# TUR8535.net
KiCad netlist of a schematic drawn in EAGLE
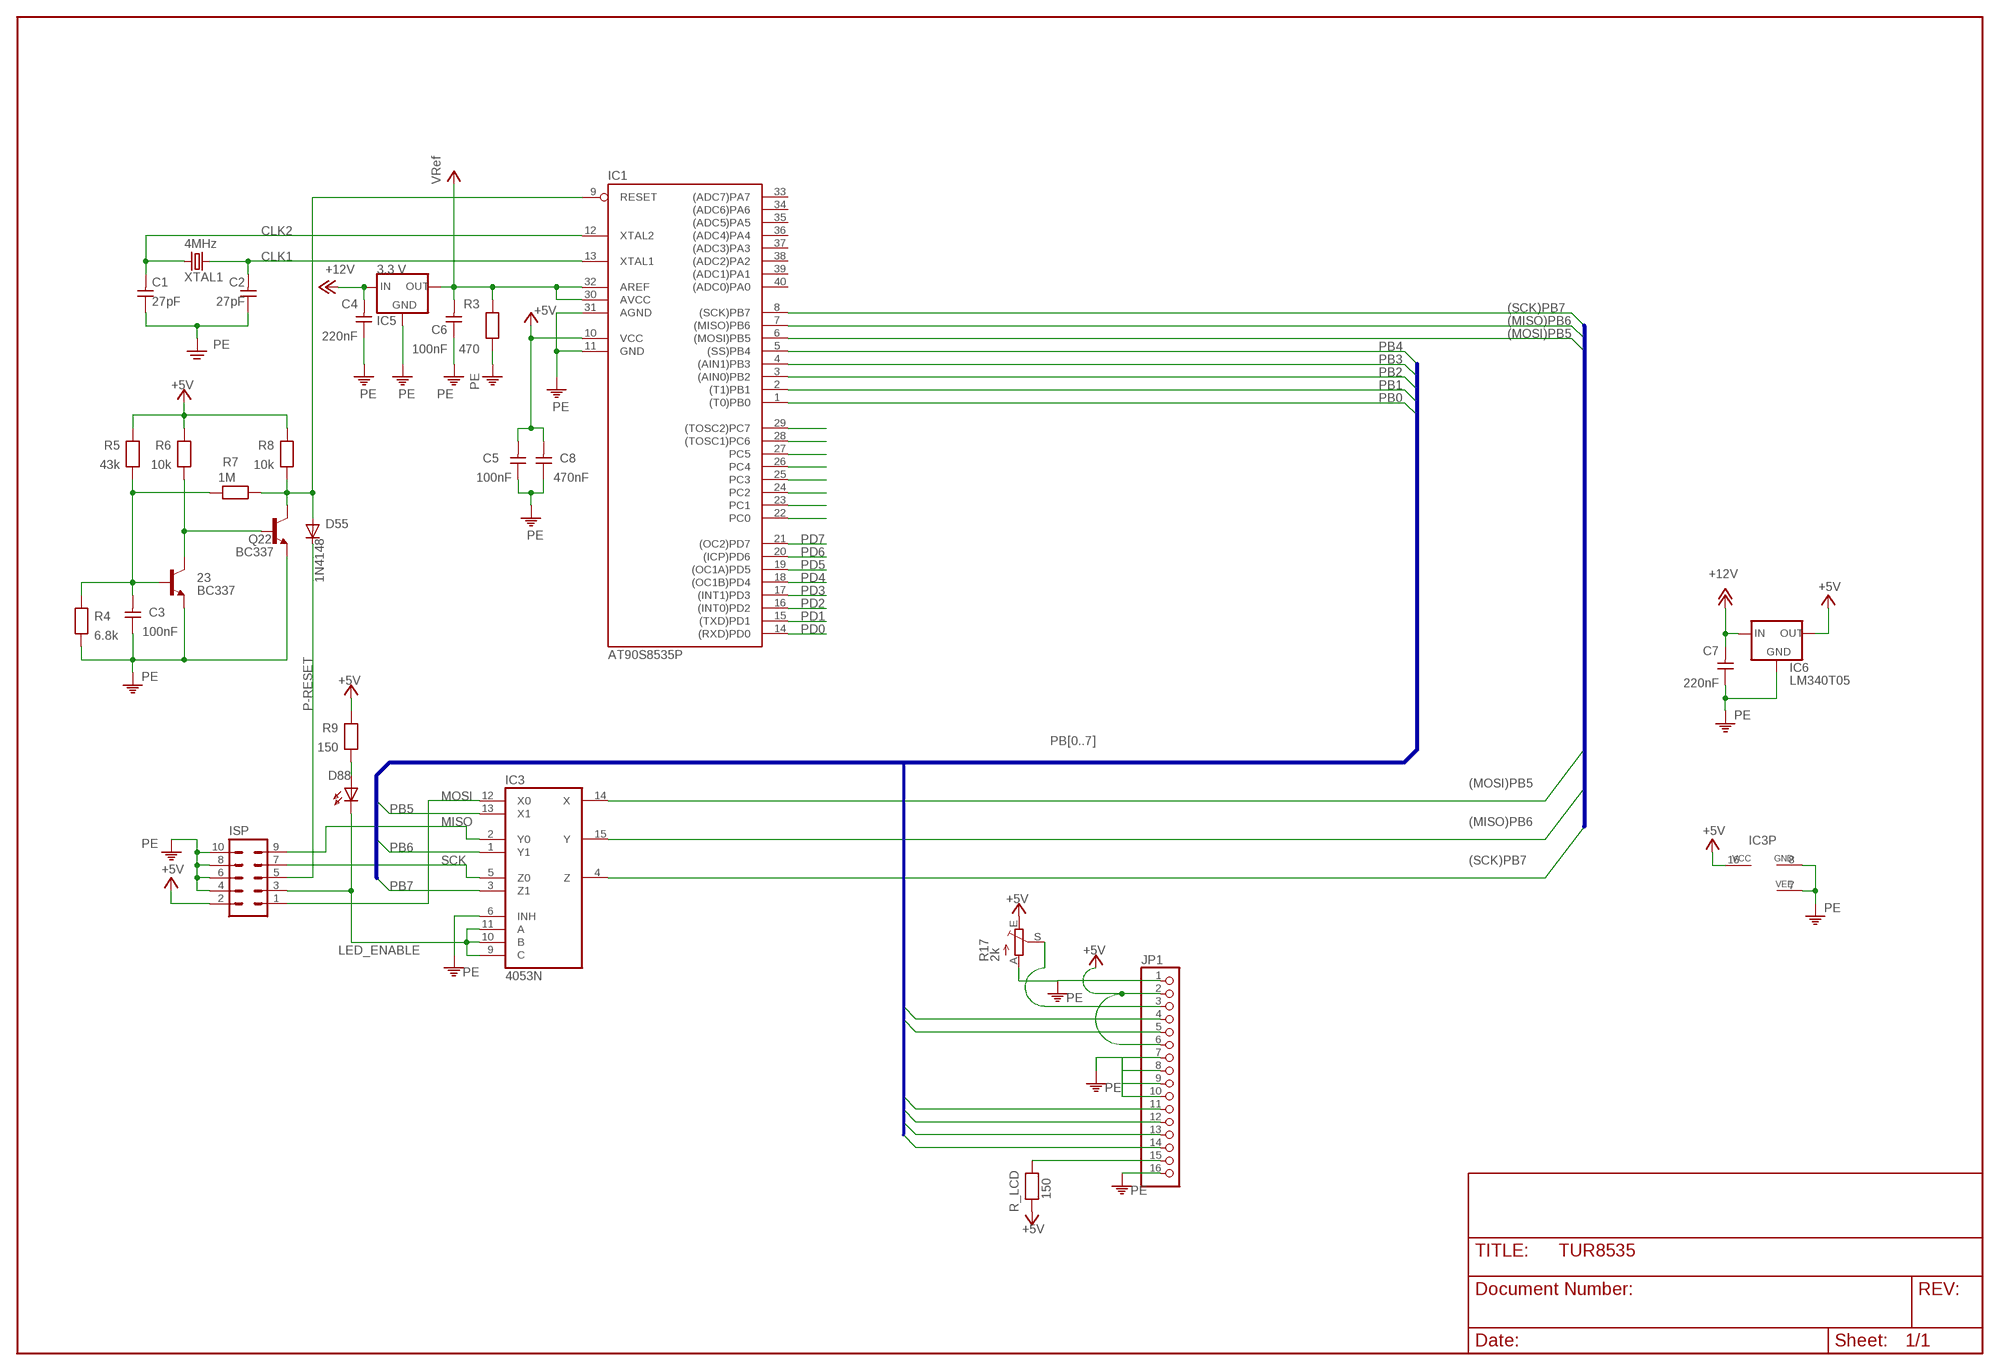
[diagram p0: schematic, sheet 1, part 1 of 2]
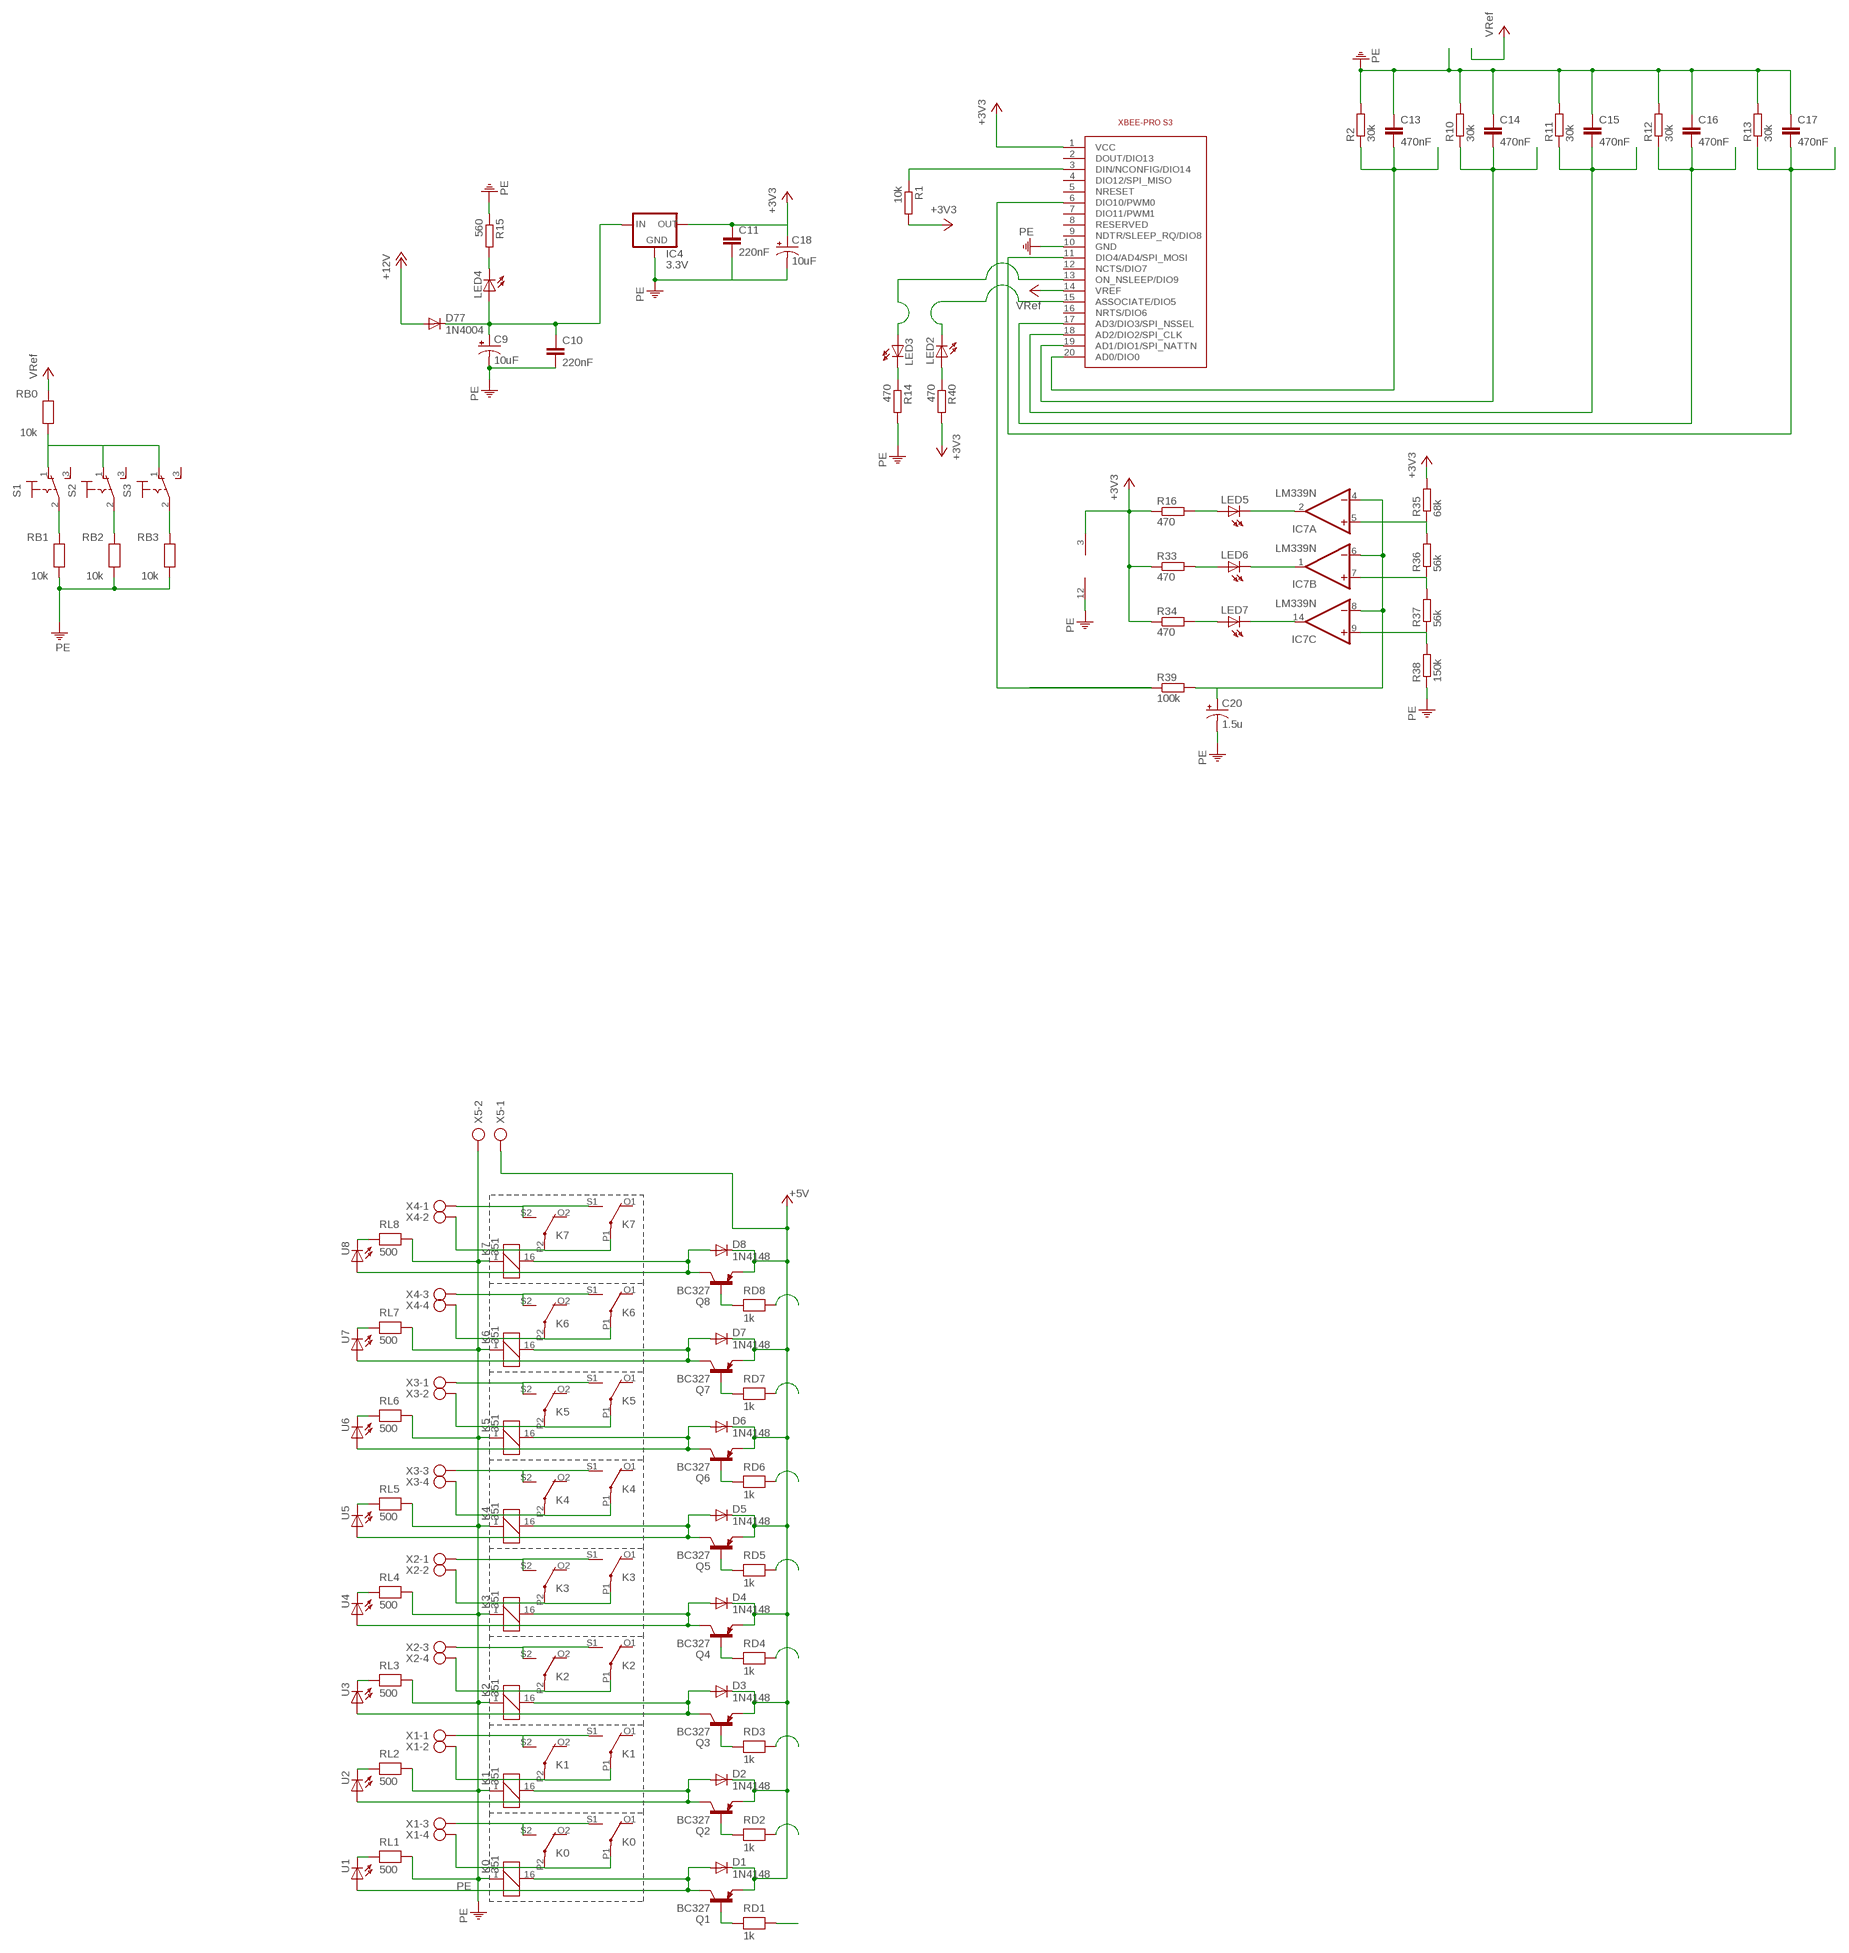
[diagram p1: schematic, sheet 1, part 2 of 2]

(export (version "E")
  (design (tool "Eeschema 10.0.6"))
  (components
    (comp (ref "23")
      (value "BC337")
      (footprint "eagle-import:TO92")
      (libsource (lib "eagle-import") (part "BC337"))
    )
    (comp (ref "C1")
      (value "27pF")
      (footprint "eagle-import:C-5")
      (libsource (lib "eagle-import") (part "CAPNP-5"))
    )
    (comp (ref "C2")
      (value "27pF")
      (footprint "eagle-import:C-5")
      (libsource (lib "eagle-import") (part "CAPNP-5"))
    )
    (comp (ref "C3")
      (value "100nF")
      (footprint "eagle-import:C-5")
      (libsource (lib "eagle-import") (part "CAPNP-5"))
    )
    (comp (ref "C4")
      (value "220nF")
      (footprint "eagle-import:C-5")
      (libsource (lib "eagle-import") (part "CAPNP-5"))
    )
    (comp (ref "C5")
      (value "100nF")
      (footprint "eagle-import:C-5")
      (libsource (lib "eagle-import") (part "CAPNP-5"))
    )
    (comp (ref "C6")
      (value "100nF")
      (footprint "eagle-import:C-5")
      (libsource (lib "eagle-import") (part "CAPNP-5"))
    )
    (comp (ref "C7")
      (value "220nF")
      (footprint "eagle-import:C-5")
      (libsource (lib "eagle-import") (part "CAPNP-5"))
    )
    (comp (ref "C8")
      (value "470nF")
      (footprint "eagle-import:C-5")
      (libsource (lib "eagle-import") (part "CAPNP-5"))
    )
    (comp (ref "C9")
      (value "10uF")
      (footprint "eagle-import:E2-5")
      (libsource (lib "eagle-import") (part "CPOL-USE2-5"))
    )
    (comp (ref "C10")
      (value "220nF")
      (footprint "eagle-import:C5B3.5")
      (libsource (lib "eagle-import") (part "C5/3.5"))
    )
    (comp (ref "C11")
      (value "220nF")
      (footprint "eagle-import:C5B3.5")
      (libsource (lib "eagle-import") (part "C5/3.5"))
    )
    (comp (ref "C13")
      (value "470nF")
      (footprint "eagle-import:C5B3.5")
      (libsource (lib "eagle-import") (part "C5/3.5"))
    )
    (comp (ref "C14")
      (value "470nF")
      (footprint "eagle-import:C5B3.5")
      (libsource (lib "eagle-import") (part "C5/3.5"))
    )
    (comp (ref "C15")
      (value "470nF")
      (footprint "eagle-import:C5B3.5")
      (libsource (lib "eagle-import") (part "C5/3.5"))
    )
    (comp (ref "C16")
      (value "470nF")
      (footprint "eagle-import:C5B3.5")
      (libsource (lib "eagle-import") (part "C5/3.5"))
    )
    (comp (ref "C17")
      (value "470nF")
      (footprint "eagle-import:C5B3.5")
      (libsource (lib "eagle-import") (part "C5/3.5"))
    )
    (comp (ref "C18")
      (value "10uF")
      (footprint "eagle-import:E2-5")
      (libsource (lib "eagle-import") (part "CPOL-USE2-5"))
    )
    (comp (ref "C20")
      (value "1.5u")
      (footprint "eagle-import:E2-5")
      (libsource (lib "eagle-import") (part "CPOL-USE2-5"))
    )
    (comp (ref "D1")
      (value "1N4148")
      (footprint "eagle-import:DO35-10")
      (libsource (lib "eagle-import") (part "1N4148"))
    )
    (comp (ref "D2")
      (value "1N4148")
      (footprint "eagle-import:DO35-10")
      (libsource (lib "eagle-import") (part "1N4148"))
    )
    (comp (ref "D3")
      (value "1N4148")
      (footprint "eagle-import:DO35-10")
      (libsource (lib "eagle-import") (part "1N4148"))
    )
    (comp (ref "D4")
      (value "1N4148")
      (footprint "eagle-import:DO35-10")
      (libsource (lib "eagle-import") (part "1N4148"))
    )
    (comp (ref "D5")
      (value "1N4148")
      (footprint "eagle-import:DO35-10")
      (libsource (lib "eagle-import") (part "1N4148"))
    )
    (comp (ref "D6")
      (value "1N4148")
      (footprint "eagle-import:DO35-10")
      (libsource (lib "eagle-import") (part "1N4148"))
    )
    (comp (ref "D7")
      (value "1N4148")
      (footprint "eagle-import:DO35-10")
      (libsource (lib "eagle-import") (part "1N4148"))
    )
    (comp (ref "D8")
      (value "1N4148")
      (footprint "eagle-import:DO35-10")
      (libsource (lib "eagle-import") (part "1N4148"))
    )
    (comp (ref "D55")
      (value "1N4148")
      (footprint "eagle-import:DO35-10")
      (libsource (lib "eagle-import") (part "1N4148"))
    )
    (comp (ref "D77")
      (value "1N4004")
      (footprint "eagle-import:DO41-10")
      (libsource (lib "eagle-import") (part "1N4004"))
    )
    (comp (ref "D88")
      (value "LED5MM")
      (footprint "eagle-import:LED5MM")
      (libsource (lib "eagle-import") (part "LED5MM"))
    )
    (comp (ref "IC1")
      (value "AT90S8535P")
      (footprint "eagle-import:DIL40")
      (libsource (lib "eagle-import") (part "AT908535PS"))
    )
    (comp (ref "IC3")
      (value "4053N")
      (footprint "eagle-import:DIL16")
      (libsource (lib "eagle-import") (part "4053N"))
    )
    (comp (ref "IC4")
      (value "3.3V")
      (footprint "eagle-import:78XXL")
      (libsource (lib "eagle-import") (part "78XXL"))
    )
    (comp (ref "IC5")
      (value "3.3 V")
      (footprint "eagle-import:78XXL")
      (libsource (lib "eagle-import") (part "78XXL"))
    )
    (comp (ref "IC6")
      (value "LM340T05")
      (footprint "eagle-import:78XXL")
      (libsource (lib "eagle-import") (part "78XXL"))
    )
    (comp (ref "IC7")
      (value "LM339N")
      (footprint "eagle-import:DIL14")
      (libsource (lib "eagle-import") (part "LM339N"))
    )
    (comp (ref "ISP")
      (value "ML10")
      (footprint "eagle-import:ML10")
      (libsource (lib "eagle-import") (part "ML10"))
    )
    (comp (ref "JP1")
      (value "PINHD-1X16")
      (footprint "eagle-import:1X16")
      (libsource (lib "eagle-import") (part "PINHD-1X16"))
    )
    (comp (ref "K0")
      (value "351")
      (footprint "eagle-import:351")
      (libsource (lib "eagle-import") (part "351"))
    )
    (comp (ref "K1")
      (value "351")
      (footprint "eagle-import:351")
      (libsource (lib "eagle-import") (part "351"))
    )
    (comp (ref "K2")
      (value "351")
      (footprint "eagle-import:351")
      (libsource (lib "eagle-import") (part "351"))
    )
    (comp (ref "K3")
      (value "351")
      (footprint "eagle-import:351")
      (libsource (lib "eagle-import") (part "351"))
    )
    (comp (ref "K4")
      (value "351")
      (footprint "eagle-import:351")
      (libsource (lib "eagle-import") (part "351"))
    )
    (comp (ref "K5")
      (value "351")
      (footprint "eagle-import:351")
      (libsource (lib "eagle-import") (part "351"))
    )
    (comp (ref "K6")
      (value "351")
      (footprint "eagle-import:351")
      (libsource (lib "eagle-import") (part "351"))
    )
    (comp (ref "K7")
      (value "351")
      (footprint "eagle-import:351")
      (libsource (lib "eagle-import") (part "351"))
    )
    (comp (ref "LED2")
      (value "LED3MM")
      (footprint "eagle-import:LED3MM")
      (libsource (lib "eagle-import") (part "LED3MM"))
    )
    (comp (ref "LED3")
      (value "LED3MM")
      (footprint "eagle-import:LED3MM")
      (libsource (lib "eagle-import") (part "LED3MM"))
    )
    (comp (ref "LED4")
      (value "LED5MM")
      (footprint "eagle-import:LED5MM")
      (libsource (lib "eagle-import") (part "LED5MM"))
    )
    (comp (ref "LED5")
      (value "LED3MM")
      (footprint "eagle-import:LED3MM")
      (libsource (lib "eagle-import") (part "LED3MM"))
    )
    (comp (ref "LED6")
      (value "LED3MM")
      (footprint "eagle-import:LED3MM")
      (libsource (lib "eagle-import") (part "LED3MM"))
    )
    (comp (ref "LED7")
      (value "LED3MM")
      (footprint "eagle-import:LED3MM")
      (libsource (lib "eagle-import") (part "LED3MM"))
    )
    (comp (ref "Q1")
      (value "BC327")
      (footprint "eagle-import:TO92-EBC")
      (libsource (lib "eagle-import") (part "BC327"))
    )
    (comp (ref "Q2")
      (value "BC327")
      (footprint "eagle-import:TO92-EBC")
      (libsource (lib "eagle-import") (part "BC327"))
    )
    (comp (ref "Q3")
      (value "BC327")
      (footprint "eagle-import:TO92-EBC")
      (libsource (lib "eagle-import") (part "BC327"))
    )
    (comp (ref "Q4")
      (value "BC327")
      (footprint "eagle-import:TO92-EBC")
      (libsource (lib "eagle-import") (part "BC327"))
    )
    (comp (ref "Q5")
      (value "BC327")
      (footprint "eagle-import:TO92-EBC")
      (libsource (lib "eagle-import") (part "BC327"))
    )
    (comp (ref "Q6")
      (value "BC327")
      (footprint "eagle-import:TO92-EBC")
      (libsource (lib "eagle-import") (part "BC327"))
    )
    (comp (ref "Q7")
      (value "BC327")
      (footprint "eagle-import:TO92-EBC")
      (libsource (lib "eagle-import") (part "BC327"))
    )
    (comp (ref "Q8")
      (value "BC327")
      (footprint "eagle-import:TO92-EBC")
      (libsource (lib "eagle-import") (part "BC327"))
    )
    (comp (ref "Q22")
      (value "BC337")
      (footprint "eagle-import:TO92")
      (libsource (lib "eagle-import") (part "BC337"))
    )
    (comp (ref "R1")
      (value "10k")
      (footprint "eagle-import:0207_7")
      (libsource (lib "eagle-import") (part "R-EU_0207/7"))
    )
    (comp (ref "R2")
      (value "30k")
      (footprint "eagle-import:0207_7")
      (libsource (lib "eagle-import") (part "R-EU_0207/7"))
    )
    (comp (ref "R3")
      (value "470")
      (footprint "eagle-import:R-10")
      (libsource (lib "eagle-import") (part "RESEU-10"))
    )
    (comp (ref "R4")
      (value "6.8k")
      (footprint "eagle-import:R-10")
      (libsource (lib "eagle-import") (part "RESEU-10"))
    )
    (comp (ref "R5")
      (value "43k")
      (footprint "eagle-import:R-10")
      (libsource (lib "eagle-import") (part "RESEU-10"))
    )
    (comp (ref "R6")
      (value "10k")
      (footprint "eagle-import:R-10")
      (libsource (lib "eagle-import") (part "RESEU-10"))
    )
    (comp (ref "R7")
      (value "1M")
      (footprint "eagle-import:R-10")
      (libsource (lib "eagle-import") (part "RESEU-10"))
    )
    (comp (ref "R8")
      (value "10k")
      (footprint "eagle-import:R-10")
      (libsource (lib "eagle-import") (part "RESEU-10"))
    )
    (comp (ref "R9")
      (value "150")
      (footprint "eagle-import:R-10")
      (libsource (lib "eagle-import") (part "RESEU-10"))
    )
    (comp (ref "R10")
      (value "30k")
      (footprint "eagle-import:0207_7")
      (libsource (lib "eagle-import") (part "R-EU_0207/7"))
    )
    (comp (ref "R11")
      (value "30k")
      (footprint "eagle-import:0207_7")
      (libsource (lib "eagle-import") (part "R-EU_0207/7"))
    )
    (comp (ref "R12")
      (value "30k")
      (footprint "eagle-import:0207_7")
      (libsource (lib "eagle-import") (part "R-EU_0207/7"))
    )
    (comp (ref "R13")
      (value "30k")
      (footprint "eagle-import:0207_7")
      (libsource (lib "eagle-import") (part "R-EU_0207/7"))
    )
    (comp (ref "R14")
      (value "470")
      (footprint "eagle-import:0207_7")
      (libsource (lib "eagle-import") (part "R-EU_0207/7"))
    )
    (comp (ref "R15")
      (value "560")
      (footprint "eagle-import:0207_7")
      (libsource (lib "eagle-import") (part "R-EU_0207/7"))
    )
    (comp (ref "R16")
      (value "470")
      (footprint "eagle-import:0207_7")
      (libsource (lib "eagle-import") (part "R-EU_0207/7"))
    )
    (comp (ref "R17")
      (value "2k")
      (footprint "eagle-import:RJ9W")
      (libsource (lib "eagle-import") (part "TRIM_EU-RJ9W"))
    )
    (comp (ref "R33")
      (value "470")
      (footprint "eagle-import:0207_7")
      (libsource (lib "eagle-import") (part "R-EU_0207/7"))
    )
    (comp (ref "R34")
      (value "470")
      (footprint "eagle-import:0207_7")
      (libsource (lib "eagle-import") (part "R-EU_0207/7"))
    )
    (comp (ref "R35")
      (value "68k")
      (footprint "eagle-import:0207_7")
      (libsource (lib "eagle-import") (part "R-EU_0207/7"))
    )
    (comp (ref "R36")
      (value "56k")
      (footprint "eagle-import:0207_7")
      (libsource (lib "eagle-import") (part "R-EU_0207/7"))
    )
    (comp (ref "R37")
      (value "56k")
      (footprint "eagle-import:0207_7")
      (libsource (lib "eagle-import") (part "R-EU_0207/7"))
    )
    (comp (ref "R38")
      (value "150k")
      (footprint "eagle-import:0207_7")
      (libsource (lib "eagle-import") (part "R-EU_0207/7"))
    )
    (comp (ref "R39")
      (value "100k")
      (footprint "eagle-import:0207_7")
      (libsource (lib "eagle-import") (part "R-EU_0207/7"))
    )
    (comp (ref "R40")
      (value "470")
      (footprint "eagle-import:0207_7")
      (libsource (lib "eagle-import") (part "R-EU_0207/7"))
    )
    (comp (ref "RB0")
      (value "10k")
      (footprint "eagle-import:R-10")
      (libsource (lib "eagle-import") (part "RESEU-10"))
    )
    (comp (ref "RB1")
      (value "10k")
      (footprint "eagle-import:R-10")
      (libsource (lib "eagle-import") (part "RESEU-10"))
    )
    (comp (ref "RB2")
      (value "10k")
      (footprint "eagle-import:R-10")
      (libsource (lib "eagle-import") (part "RESEU-10"))
    )
    (comp (ref "RB3")
      (value "10k")
      (footprint "eagle-import:R-10")
      (libsource (lib "eagle-import") (part "RESEU-10"))
    )
    (comp (ref "RD1")
      (value "1k")
      (footprint "eagle-import:R-10")
      (libsource (lib "eagle-import") (part "RESEU-10"))
    )
    (comp (ref "RD2")
      (value "1k")
      (footprint "eagle-import:R-10")
      (libsource (lib "eagle-import") (part "RESEU-10"))
    )
    (comp (ref "RD3")
      (value "1k")
      (footprint "eagle-import:R-10")
      (libsource (lib "eagle-import") (part "RESEU-10"))
    )
    (comp (ref "RD4")
      (value "1k")
      (footprint "eagle-import:R-10")
      (libsource (lib "eagle-import") (part "RESEU-10"))
    )
    (comp (ref "RD5")
      (value "1k")
      (footprint "eagle-import:R-10")
      (libsource (lib "eagle-import") (part "RESEU-10"))
    )
    (comp (ref "RD6")
      (value "1k")
      (footprint "eagle-import:R-10")
      (libsource (lib "eagle-import") (part "RESEU-10"))
    )
    (comp (ref "RD7")
      (value "1k")
      (footprint "eagle-import:R-10")
      (libsource (lib "eagle-import") (part "RESEU-10"))
    )
    (comp (ref "RD8")
      (value "1k")
      (footprint "eagle-import:R-10")
      (libsource (lib "eagle-import") (part "RESEU-10"))
    )
    (comp (ref "RL1")
      (value "500")
      (footprint "eagle-import:R-10")
      (libsource (lib "eagle-import") (part "RESEU-10"))
    )
    (comp (ref "RL2")
      (value "500")
      (footprint "eagle-import:R-10")
      (libsource (lib "eagle-import") (part "RESEU-10"))
    )
    (comp (ref "RL3")
      (value "500")
      (footprint "eagle-import:R-10")
      (libsource (lib "eagle-import") (part "RESEU-10"))
    )
    (comp (ref "RL4")
      (value "500")
      (footprint "eagle-import:R-10")
      (libsource (lib "eagle-import") (part "RESEU-10"))
    )
    (comp (ref "RL5")
      (value "500")
      (footprint "eagle-import:R-10")
      (libsource (lib "eagle-import") (part "RESEU-10"))
    )
    (comp (ref "RL6")
      (value "500")
      (footprint "eagle-import:R-10")
      (libsource (lib "eagle-import") (part "RESEU-10"))
    )
    (comp (ref "RL7")
      (value "500")
      (footprint "eagle-import:R-10")
      (libsource (lib "eagle-import") (part "RESEU-10"))
    )
    (comp (ref "RL8")
      (value "500")
      (footprint "eagle-import:R-10")
      (libsource (lib "eagle-import") (part "RESEU-10"))
    )
    (comp (ref "R_LCD")
      (value "150")
      (footprint "eagle-import:R-10")
      (libsource (lib "eagle-import") (part "RESEU-10"))
    )
    (comp (ref "S1")
      (value "320-916")
      (footprint "eagle-import:320-916")
      (libsource (lib "eagle-import") (part "320-916"))
    )
    (comp (ref "S2")
      (value "320-916")
      (footprint "eagle-import:320-916")
      (libsource (lib "eagle-import") (part "320-916"))
    )
    (comp (ref "S3")
      (value "320-916")
      (footprint "eagle-import:320-916")
      (libsource (lib "eagle-import") (part "320-916"))
    )
    (comp (ref "U$1")
      (value "XBEEPRO900")
      (footprint "eagle-import:XBEE-PRO")
      (libsource (lib "eagle-import") (part "XBEEPRO900"))
    )
    (comp (ref "U1")
      (value "LED3MM")
      (footprint "eagle-import:LED3MM")
      (libsource (lib "eagle-import") (part "LED3MM"))
    )
    (comp (ref "U2")
      (value "LED3MM")
      (footprint "eagle-import:LED3MM")
      (libsource (lib "eagle-import") (part "LED3MM"))
    )
    (comp (ref "U3")
      (value "LED3MM")
      (footprint "eagle-import:LED3MM")
      (libsource (lib "eagle-import") (part "LED3MM"))
    )
    (comp (ref "U4")
      (value "LED3MM")
      (footprint "eagle-import:LED3MM")
      (libsource (lib "eagle-import") (part "LED3MM"))
    )
    (comp (ref "U5")
      (value "LED3MM")
      (footprint "eagle-import:LED3MM")
      (libsource (lib "eagle-import") (part "LED3MM"))
    )
    (comp (ref "U6")
      (value "LED3MM")
      (footprint "eagle-import:LED3MM")
      (libsource (lib "eagle-import") (part "LED3MM"))
    )
    (comp (ref "U7")
      (value "LED3MM")
      (footprint "eagle-import:LED3MM")
      (libsource (lib "eagle-import") (part "LED3MM"))
    )
    (comp (ref "U8")
      (value "LED3MM")
      (footprint "eagle-import:LED3MM")
      (libsource (lib "eagle-import") (part "LED3MM"))
    )
    (comp (ref "X1")
      (value "AK500/4-H")
      (footprint "eagle-import:AK500_4-H")
      (libsource (lib "eagle-import") (part "AK500/4-H"))
    )
    (comp (ref "X2")
      (value "AK500/4-H")
      (footprint "eagle-import:AK500_4-H")
      (libsource (lib "eagle-import") (part "AK500/4-H"))
    )
    (comp (ref "X3")
      (value "AK500/4-H")
      (footprint "eagle-import:AK500_4-H")
      (libsource (lib "eagle-import") (part "AK500/4-H"))
    )
    (comp (ref "X4")
      (value "AK500/4-H")
      (footprint "eagle-import:AK500_4-H")
      (libsource (lib "eagle-import") (part "AK500/4-H"))
    )
    (comp (ref "X5")
      (value "AK500/2")
      (footprint "eagle-import:AK500_2")
      (libsource (lib "eagle-import") (part "AK500/2"))
    )
    (comp (ref "XTAL1")
      (value "4MHz")
      (footprint "eagle-import:HC18U-V")
      (libsource (lib "eagle-import") (part "CRYTALHC18U-V"))
    )
  )
  (nets
    (net (code "1") (name "+3V3") (class "Default")
      (node (ref "C11") (pin "1") (pinfunction "1_1") (pintype "passive"))
      (node (ref "C18") (pin "+") (pinfunction "+_+") (pintype "passive"))
      (node (ref "IC4") (pin "OUT") (pinfunction "OUT_OUT") (pintype "passive"))
      (node (ref "IC7") (pin "3") (pinfunction "V+_3") (pintype "power_in"))
      (node (ref "R1") (pin "2") (pinfunction "2_2") (pintype "passive"))
      (node (ref "R16") (pin "1") (pinfunction "1_1") (pintype "passive"))
      (node (ref "R33") (pin "1") (pinfunction "1_1") (pintype "passive"))
      (node (ref "R34") (pin "1") (pinfunction "1_1") (pintype "passive"))
      (node (ref "R35") (pin "2") (pinfunction "2_2") (pintype "passive"))
      (node (ref "R40") (pin "2") (pinfunction "2_2") (pintype "passive"))
      (node (ref "U$1") (pin "1") (pinfunction "VCC_1") (pintype "input"))
    )
    (net (code "2") (name "+5V") (class "Default")
      (node (ref "C5") (pin "2") (pinfunction "2_2") (pintype "passive"))
      (node (ref "C8") (pin "2") (pinfunction "2_2") (pintype "passive"))
      (node (ref "D1") (pin "C") (pinfunction "C_C") (pintype "passive"))
      (node (ref "D2") (pin "C") (pinfunction "C_C") (pintype "passive"))
      (node (ref "D3") (pin "C") (pinfunction "C_C") (pintype "passive"))
      (node (ref "D4") (pin "C") (pinfunction "C_C") (pintype "passive"))
      (node (ref "D5") (pin "C") (pinfunction "C_C") (pintype "passive"))
      (node (ref "D6") (pin "C") (pinfunction "C_C") (pintype "passive"))
      (node (ref "D7") (pin "C") (pinfunction "C_C") (pintype "passive"))
      (node (ref "D8") (pin "C") (pinfunction "C_C") (pintype "passive"))
      (node (ref "IC1") (pin "10") (pinfunction "VCC_10") (pintype "power_in"))
      (node (ref "IC3") (pin "16") (pinfunction "VCC_16") (pintype "power_in"))
      (node (ref "IC6") (pin "OUT") (pinfunction "OUT_OUT") (pintype "passive"))
      (node (ref "ISP") (pin "2") (pinfunction "2_2") (pintype "passive"))
      (node (ref "JP1") (pin "2") (pinfunction "2_2") (pintype "passive"))
      (node (ref "JP1") (pin "6") (pinfunction "6_6") (pintype "passive"))
      (node (ref "Q1") (pin "E") (pinfunction "E_E") (pintype "passive"))
      (node (ref "Q2") (pin "E") (pinfunction "E_E") (pintype "passive"))
      (node (ref "Q3") (pin "E") (pinfunction "E_E") (pintype "passive"))
      (node (ref "Q4") (pin "E") (pinfunction "E_E") (pintype "passive"))
      (node (ref "Q5") (pin "E") (pinfunction "E_E") (pintype "passive"))
      (node (ref "Q6") (pin "E") (pinfunction "E_E") (pintype "passive"))
      (node (ref "Q7") (pin "E") (pinfunction "E_E") (pintype "passive"))
      (node (ref "Q8") (pin "E") (pinfunction "E_E") (pintype "passive"))
      (node (ref "R17") (pin "E") (pinfunction "E_E") (pintype "passive"))
      (node (ref "R5") (pin "2") (pinfunction "2_2") (pintype "passive"))
      (node (ref "R6") (pin "2") (pinfunction "2_2") (pintype "passive"))
      (node (ref "R8") (pin "2") (pinfunction "2_2") (pintype "passive"))
      (node (ref "R9") (pin "2") (pinfunction "2_2") (pintype "passive"))
      (node (ref "R_LCD") (pin "2") (pinfunction "2_2") (pintype "passive"))
      (node (ref "X5") (pin "1") (pinfunction "KL_1") (pintype "passive"))
    )
    (net (code "3") (name "+12V") (class "Default")
      (node (ref "C4") (pin "2") (pinfunction "2_2") (pintype "passive"))
      (node (ref "C7") (pin "2") (pinfunction "2_2") (pintype "passive"))
      (node (ref "D77") (pin "A") (pinfunction "A_A") (pintype "passive"))
      (node (ref "IC5") (pin "IN") (pinfunction "IN_IN") (pintype "input"))
      (node (ref "IC6") (pin "IN") (pinfunction "IN_IN") (pintype "input"))
    )
    (net (code "4") (name "/(MISO)PB6") (class "Default")
      (node (ref "IC1") (pin "7") (pinfunction "(MISO)PB6_7") (pintype "bidirectional"))
      (node (ref "IC3") (pin "15") (pinfunction "Y_15") (pintype "bidirectional"))
    )
    (net (code "5") (name "/(MOSI)PB5") (class "Default")
      (node (ref "IC1") (pin "6") (pinfunction "(MOSI)PB5_6") (pintype "bidirectional"))
      (node (ref "IC3") (pin "14") (pinfunction "X_14") (pintype "bidirectional"))
    )
    (net (code "6") (name "/(SCK)PB7") (class "Default")
      (node (ref "IC1") (pin "8") (pinfunction "(SCK)PB7_8") (pintype "bidirectional"))
      (node (ref "IC3") (pin "4") (pinfunction "Z_4") (pintype "bidirectional"))
    )
    (net (code "7") (name "/CLK1") (class "Default")
      (node (ref "C2") (pin "2") (pinfunction "2_2") (pintype "passive"))
      (node (ref "IC1") (pin "13") (pinfunction "XTAL1_13") (pintype "bidirectional"))
      (node (ref "XTAL1") (pin "2") (pinfunction "2_2") (pintype "passive"))
    )
    (net (code "8") (name "/CLK2") (class "Default")
      (node (ref "C1") (pin "2") (pinfunction "2_2") (pintype "passive"))
      (node (ref "IC1") (pin "12") (pinfunction "XTAL2_12") (pintype "bidirectional"))
      (node (ref "XTAL1") (pin "1") (pinfunction "1_1") (pintype "passive"))
    )
    (net (code "9") (name "/LED_ENABLE") (class "Default")
      (node (ref "D88") (pin "K") (pinfunction "C_K") (pintype "passive"))
      (node (ref "IC3") (pin "10") (pinfunction "B_10") (pintype "input"))
      (node (ref "IC3") (pin "11") (pinfunction "A_11") (pintype "input"))
      (node (ref "IC3") (pin "9") (pinfunction "C_9") (pintype "input"))
      (node (ref "ISP") (pin "3") (pinfunction "3_3") (pintype "passive"))
    )
    (net (code "10") (name "/MISO") (class "Default")
      (node (ref "IC3") (pin "2") (pinfunction "Y0_2") (pintype "bidirectional"))
      (node (ref "ISP") (pin "9") (pinfunction "9_9") (pintype "passive"))
    )
    (net (code "11") (name "/MOSI") (class "Default")
      (node (ref "IC3") (pin "12") (pinfunction "X0_12") (pintype "bidirectional"))
      (node (ref "ISP") (pin "1") (pinfunction "1_1") (pintype "passive"))
    )
    (net (code "12") (name "/P-RESET") (class "Default")
      (node (ref "D55") (pin "C") (pinfunction "C_C") (pintype "passive"))
      (node (ref "ISP") (pin "5") (pinfunction "5_5") (pintype "passive"))
    )
    (net (code "13") (name "/PB0") (class "Default")
      (node (ref "IC1") (pin "1") (pinfunction "(T0)PB0_1") (pintype "bidirectional"))
      (node (ref "JP1") (pin "5") (pinfunction "5_5") (pintype "passive"))
    )
    (net (code "14") (name "/PB1") (class "Default")
      (node (ref "IC1") (pin "2") (pinfunction "(T1)PB1_2") (pintype "bidirectional"))
      (node (ref "JP1") (pin "4") (pinfunction "4_4") (pintype "passive"))
    )
    (net (code "15") (name "/PB2") (class "Default")
      (node (ref "IC1") (pin "3") (pinfunction "(AIN0)PB2_3") (pintype "bidirectional"))
    )
    (net (code "16") (name "/PB3") (class "Default")
      (node (ref "IC1") (pin "4") (pinfunction "(AIN1)PB3_4") (pintype "bidirectional"))
    )
    (net (code "17") (name "/PB4") (class "Default")
      (node (ref "IC1") (pin "5") (pinfunction "(SS)PB4_5") (pintype "bidirectional"))
      (node (ref "JP1") (pin "11") (pinfunction "11_11") (pintype "passive"))
    )
    (net (code "18") (name "/PB5") (class "Default")
      (node (ref "IC3") (pin "13") (pinfunction "X1_13") (pintype "bidirectional"))
      (node (ref "JP1") (pin "12") (pinfunction "12_12") (pintype "passive"))
    )
    (net (code "19") (name "/PB6") (class "Default")
      (node (ref "IC3") (pin "1") (pinfunction "Y1_1") (pintype "bidirectional"))
      (node (ref "JP1") (pin "13") (pinfunction "13_13") (pintype "passive"))
    )
    (net (code "20") (name "/PB7") (class "Default")
      (node (ref "IC3") (pin "3") (pinfunction "Z1_3") (pintype "bidirectional"))
      (node (ref "JP1") (pin "14") (pinfunction "14_14") (pintype "passive"))
    )
    (net (code "22") (name "/PC0") (class "Default")
      (node (ref "IC1") (pin "22") (pinfunction "PC0_22") (pintype "bidirectional"))
      (node (ref "RD8") (pin "2") (pinfunction "2_2") (pintype "passive"))
    )
    (net (code "23") (name "/PC1") (class "Default")
      (node (ref "IC1") (pin "23") (pinfunction "PC1_23") (pintype "bidirectional"))
      (node (ref "RD7") (pin "2") (pinfunction "2_2") (pintype "passive"))
    )
    (net (code "24") (name "/PC2") (class "Default")
      (node (ref "IC1") (pin "24") (pinfunction "PC2_24") (pintype "bidirectional"))
      (node (ref "RD6") (pin "2") (pinfunction "2_2") (pintype "passive"))
    )
    (net (code "25") (name "/PC3") (class "Default")
      (node (ref "IC1") (pin "25") (pinfunction "PC3_25") (pintype "bidirectional"))
      (node (ref "RD5") (pin "2") (pinfunction "2_2") (pintype "passive"))
    )
    (net (code "26") (name "/PC4") (class "Default")
      (node (ref "IC1") (pin "26") (pinfunction "PC4_26") (pintype "bidirectional"))
      (node (ref "RD4") (pin "2") (pinfunction "2_2") (pintype "passive"))
    )
    (net (code "27") (name "/PC5") (class "Default")
      (node (ref "IC1") (pin "27") (pinfunction "PC5_27") (pintype "bidirectional"))
      (node (ref "RD3") (pin "2") (pinfunction "2_2") (pintype "passive"))
    )
    (net (code "28") (name "/PC6") (class "Default")
      (node (ref "IC1") (pin "28") (pinfunction "(TOSC1)PC6_28") (pintype "bidirectional"))
      (node (ref "RD2") (pin "2") (pinfunction "2_2") (pintype "passive"))
    )
    (net (code "29") (name "/PC7") (class "Default")
      (node (ref "IC1") (pin "29") (pinfunction "(TOSC2)PC7_29") (pintype "bidirectional"))
      (node (ref "RD1") (pin "2") (pinfunction "2_2") (pintype "passive"))
    )
    (net (code "30") (name "/PD0") (class "Default")
      (node (ref "IC1") (pin "14") (pinfunction "(RXD)PD0_14") (pintype "bidirectional"))
    )
    (net (code "31") (name "/PD1") (class "Default")
      (node (ref "IC1") (pin "15") (pinfunction "(TXD)PD1_15") (pintype "bidirectional"))
    )
    (net (code "32") (name "/PD2") (class "Default")
      (node (ref "IC1") (pin "16") (pinfunction "(INT0)PD2_16") (pintype "bidirectional"))
    )
    (net (code "33") (name "/PD3") (class "Default")
      (node (ref "IC1") (pin "17") (pinfunction "(INT1)PD3_17") (pintype "bidirectional"))
    )
    (net (code "34") (name "/PD4") (class "Default")
      (node (ref "IC1") (pin "18") (pinfunction "(OC1B)PD4_18") (pintype "bidirectional"))
    )
    (net (code "35") (name "/PD5") (class "Default")
      (node (ref "IC1") (pin "19") (pinfunction "(OC1A)PD5_19") (pintype "bidirectional"))
    )
    (net (code "36") (name "/PD6") (class "Default")
      (node (ref "IC1") (pin "20") (pinfunction "(ICP)PD6_20") (pintype "bidirectional"))
    )
    (net (code "37") (name "/PD7") (class "Default")
      (node (ref "IC1") (pin "21") (pinfunction "(OC2)PD7_21") (pintype "bidirectional"))
    )
    (net (code "38") (name "/SCK") (class "Default")
      (node (ref "IC3") (pin "5") (pinfunction "Z0_5") (pintype "bidirectional"))
      (node (ref "ISP") (pin "7") (pinfunction "7_7") (pintype "passive"))
    )
    (net (code "39") (name "Net-(23-B)") (class "Default")
      (node (ref "23") (pin "2") (pinfunction "B_2") (pintype "passive"))
      (node (ref "C3") (pin "2") (pinfunction "2_2") (pintype "passive"))
      (node (ref "R4") (pin "2") (pinfunction "2_2") (pintype "passive"))
      (node (ref "R5") (pin "1") (pinfunction "1_1") (pintype "passive"))
      (node (ref "R7") (pin "1") (pinfunction "1_1") (pintype "passive"))
    )
    (net (code "40") (name "Net-(23-C)") (class "Default")
      (node (ref "23") (pin "3") (pinfunction "C_3") (pintype "passive"))
      (node (ref "Q22") (pin "2") (pinfunction "B_2") (pintype "passive"))
      (node (ref "R6") (pin "1") (pinfunction "1_1") (pintype "passive"))
    )
    (net (code "41") (name "Net-(C10-Pad1)") (class "Default")
      (node (ref "C10") (pin "1") (pinfunction "1_1") (pintype "passive"))
      (node (ref "C9") (pin "+") (pinfunction "+_+") (pintype "passive"))
      (node (ref "D77") (pin "C") (pinfunction "C_C") (pintype "passive"))
      (node (ref "IC4") (pin "IN") (pinfunction "IN_IN") (pintype "input"))
      (node (ref "LED4") (pin "A") (pinfunction "A_A") (pintype "passive"))
    )
    (net (code "42") (name "Net-(D88-PadA)") (class "Default")
      (node (ref "D88") (pin "A") (pinfunction "A_A") (pintype "passive"))
      (node (ref "R9") (pin "1") (pinfunction "1_1") (pintype "passive"))
    )
    (net (code "43") (name "Net-(IC1-RESET)") (class "Default")
      (node (ref "D55") (pin "A") (pinfunction "A_A") (pintype "passive"))
      (node (ref "IC1") (pin "9") (pinfunction "RESET_9") (pintype "input"))
      (node (ref "Q22") (pin "3") (pinfunction "C_3") (pintype "passive"))
      (node (ref "R7") (pin "2") (pinfunction "2_2") (pintype "passive"))
      (node (ref "R8") (pin "1") (pinfunction "1_1") (pintype "passive"))
    )
    (net (code "44") (name "Net-(IC7A-+IN)") (class "Default")
      (node (ref "IC7") (pin "5") (pinfunction "+IN_5") (pintype "input"))
      (node (ref "R35") (pin "1") (pinfunction "1_1") (pintype "passive"))
      (node (ref "R36") (pin "2") (pinfunction "2_2") (pintype "passive"))
    )
    (net (code "45") (name "Net-(IC7A--IN)") (class "Default")
      (node (ref "C20") (pin "+") (pinfunction "+_+") (pintype "passive"))
      (node (ref "IC7") (pin "4") (pinfunction "-IN_4") (pintype "input"))
      (node (ref "IC7") (pin "6") (pinfunction "-IN_6") (pintype "input"))
      (node (ref "IC7") (pin "8") (pinfunction "-IN_8") (pintype "input"))
      (node (ref "R39") (pin "2") (pinfunction "2_2") (pintype "passive"))
    )
    (net (code "46") (name "Net-(IC7A-OUT)") (class "Default")
      (node (ref "IC7") (pin "2") (pinfunction "OUT_2") (pintype "open_collector"))
      (node (ref "LED5") (pin "K") (pinfunction "C_K") (pintype "passive"))
    )
    (net (code "47") (name "Net-(IC7B-+IN)") (class "Default")
      (node (ref "IC7") (pin "7") (pinfunction "+IN_7") (pintype "input"))
      (node (ref "R36") (pin "1") (pinfunction "1_1") (pintype "passive"))
      (node (ref "R37") (pin "2") (pinfunction "2_2") (pintype "passive"))
    )
    (net (code "48") (name "Net-(IC7B-OUT)") (class "Default")
      (node (ref "IC7") (pin "1") (pinfunction "OUT_1") (pintype "open_collector"))
      (node (ref "LED6") (pin "K") (pinfunction "C_K") (pintype "passive"))
    )
    (net (code "49") (name "Net-(IC7C-+IN)") (class "Default")
      (node (ref "IC7") (pin "9") (pinfunction "+IN_9") (pintype "input"))
      (node (ref "R37") (pin "1") (pinfunction "1_1") (pintype "passive"))
      (node (ref "R38") (pin "2") (pinfunction "2_2") (pintype "passive"))
    )
    (net (code "50") (name "Net-(IC7C-OUT)") (class "Default")
      (node (ref "IC7") (pin "14") (pinfunction "OUT_14") (pintype "open_collector"))
      (node (ref "LED7") (pin "K") (pinfunction "C_K") (pintype "passive"))
    )
    (net (code "51") (name "Net-(JP1-Pad3)") (class "Default")
      (node (ref "JP1") (pin "3") (pinfunction "3_3") (pintype "passive"))
      (node (ref "R17") (pin "S") (pinfunction "S_S") (pintype "passive"))
    )
    (net (code "52") (name "Net-(JP1-Pad15)") (class "Default")
      (node (ref "JP1") (pin "15") (pinfunction "15_15") (pintype "passive"))
      (node (ref "R_LCD") (pin "1") (pinfunction "1_1") (pintype "passive"))
    )
    (net (code "53") (name "Net-(K0A-2)") (class "Default")
      (node (ref "D1") (pin "A") (pinfunction "A_A") (pintype "passive"))
      (node (ref "K0") (pin "16") (pinfunction "2_16") (pintype "passive"))
      (node (ref "Q1") (pin "C") (pinfunction "C_C") (pintype "passive"))
      (node (ref "U1") (pin "A") (pinfunction "A_A") (pintype "passive"))
    )
    (net (code "54") (name "Net-(K0B-P)") (class "Default")
      (node (ref "K0") (pin "P1") (pinfunction "P_P1") (pintype "passive"))
      (node (ref "K0") (pin "P2") (pinfunction "P_P2") (pintype "passive"))
      (node (ref "X1") (pin "4") (pinfunction "KL_4") (pintype "passive"))
    )
    (net (code "55") (name "Net-(K0B-S)") (class "Default")
      (node (ref "K0") (pin "S1") (pinfunction "S_S1") (pintype "passive"))
      (node (ref "K0") (pin "S2") (pinfunction "S_S2") (pintype "passive"))
      (node (ref "X1") (pin "3") (pinfunction "KL_3") (pintype "passive"))
    )
    (net (code "56") (name "Net-(K1A-2)") (class "Default")
      (node (ref "D2") (pin "A") (pinfunction "A_A") (pintype "passive"))
      (node (ref "K1") (pin "16") (pinfunction "2_16") (pintype "passive"))
      (node (ref "Q2") (pin "C") (pinfunction "C_C") (pintype "passive"))
      (node (ref "U2") (pin "A") (pinfunction "A_A") (pintype "passive"))
    )
    (net (code "57") (name "Net-(K1B-P)") (class "Default")
      (node (ref "K1") (pin "P1") (pinfunction "P_P1") (pintype "passive"))
      (node (ref "K1") (pin "P2") (pinfunction "P_P2") (pintype "passive"))
      (node (ref "X1") (pin "2") (pinfunction "KL_2") (pintype "passive"))
    )
    (net (code "58") (name "Net-(K1B-S)") (class "Default")
      (node (ref "K1") (pin "S1") (pinfunction "S_S1") (pintype "passive"))
      (node (ref "K1") (pin "S2") (pinfunction "S_S2") (pintype "passive"))
      (node (ref "X1") (pin "1") (pinfunction "KL_1") (pintype "passive"))
    )
    (net (code "59") (name "Net-(K2A-2)") (class "Default")
      (node (ref "D3") (pin "A") (pinfunction "A_A") (pintype "passive"))
      (node (ref "K2") (pin "16") (pinfunction "2_16") (pintype "passive"))
      (node (ref "Q3") (pin "C") (pinfunction "C_C") (pintype "passive"))
      (node (ref "U3") (pin "A") (pinfunction "A_A") (pintype "passive"))
    )
    (net (code "60") (name "Net-(K2B-P)") (class "Default")
      (node (ref "K2") (pin "P1") (pinfunction "P_P1") (pintype "passive"))
      (node (ref "K2") (pin "P2") (pinfunction "P_P2") (pintype "passive"))
      (node (ref "X2") (pin "4") (pinfunction "KL_4") (pintype "passive"))
    )
    (net (code "61") (name "Net-(K2B-S)") (class "Default")
      (node (ref "K2") (pin "S1") (pinfunction "S_S1") (pintype "passive"))
      (node (ref "K2") (pin "S2") (pinfunction "S_S2") (pintype "passive"))
      (node (ref "X2") (pin "3") (pinfunction "KL_3") (pintype "passive"))
    )
    (net (code "62") (name "Net-(K3A-2)") (class "Default")
      (node (ref "D4") (pin "A") (pinfunction "A_A") (pintype "passive"))
      (node (ref "K3") (pin "16") (pinfunction "2_16") (pintype "passive"))
      (node (ref "Q4") (pin "C") (pinfunction "C_C") (pintype "passive"))
      (node (ref "U4") (pin "A") (pinfunction "A_A") (pintype "passive"))
    )
    (net (code "63") (name "Net-(K3B-P)") (class "Default")
      (node (ref "K3") (pin "P1") (pinfunction "P_P1") (pintype "passive"))
      (node (ref "K3") (pin "P2") (pinfunction "P_P2") (pintype "passive"))
      (node (ref "X2") (pin "2") (pinfunction "KL_2") (pintype "passive"))
    )
    (net (code "64") (name "Net-(K3B-S)") (class "Default")
      (node (ref "K3") (pin "S1") (pinfunction "S_S1") (pintype "passive"))
      (node (ref "K3") (pin "S2") (pinfunction "S_S2") (pintype "passive"))
      (node (ref "X2") (pin "1") (pinfunction "KL_1") (pintype "passive"))
    )
    (net (code "65") (name "Net-(K4A-2)") (class "Default")
      (node (ref "D5") (pin "A") (pinfunction "A_A") (pintype "passive"))
      (node (ref "K4") (pin "16") (pinfunction "2_16") (pintype "passive"))
      (node (ref "Q5") (pin "C") (pinfunction "C_C") (pintype "passive"))
      (node (ref "U5") (pin "A") (pinfunction "A_A") (pintype "passive"))
    )
    (net (code "66") (name "Net-(K4B-P)") (class "Default")
      (node (ref "K4") (pin "P1") (pinfunction "P_P1") (pintype "passive"))
      (node (ref "K4") (pin "P2") (pinfunction "P_P2") (pintype "passive"))
      (node (ref "X3") (pin "4") (pinfunction "KL_4") (pintype "passive"))
    )
    (net (code "67") (name "Net-(K4B-S)") (class "Default")
      (node (ref "K4") (pin "S1") (pinfunction "S_S1") (pintype "passive"))
      (node (ref "K4") (pin "S2") (pinfunction "S_S2") (pintype "passive"))
      (node (ref "X3") (pin "3") (pinfunction "KL_3") (pintype "passive"))
    )
    (net (code "68") (name "Net-(K5A-2)") (class "Default")
      (node (ref "D6") (pin "A") (pinfunction "A_A") (pintype "passive"))
      (node (ref "K5") (pin "16") (pinfunction "2_16") (pintype "passive"))
      (node (ref "Q6") (pin "C") (pinfunction "C_C") (pintype "passive"))
      (node (ref "U6") (pin "A") (pinfunction "A_A") (pintype "passive"))
    )
    (net (code "69") (name "Net-(K5B-P)") (class "Default")
      (node (ref "K5") (pin "P1") (pinfunction "P_P1") (pintype "passive"))
      (node (ref "K5") (pin "P2") (pinfunction "P_P2") (pintype "passive"))
      (node (ref "X3") (pin "2") (pinfunction "KL_2") (pintype "passive"))
    )
    (net (code "70") (name "Net-(K5B-S)") (class "Default")
      (node (ref "K5") (pin "S1") (pinfunction "S_S1") (pintype "passive"))
      (node (ref "K5") (pin "S2") (pinfunction "S_S2") (pintype "passive"))
      (node (ref "X3") (pin "1") (pinfunction "KL_1") (pintype "passive"))
    )
    (net (code "71") (name "Net-(K6A-2)") (class "Default")
      (node (ref "D7") (pin "A") (pinfunction "A_A") (pintype "passive"))
      (node (ref "K6") (pin "16") (pinfunction "2_16") (pintype "passive"))
      (node (ref "Q7") (pin "C") (pinfunction "C_C") (pintype "passive"))
      (node (ref "U7") (pin "A") (pinfunction "A_A") (pintype "passive"))
    )
    (net (code "72") (name "Net-(K6B-P)") (class "Default")
      (node (ref "K6") (pin "P1") (pinfunction "P_P1") (pintype "passive"))
      (node (ref "K6") (pin "P2") (pinfunction "P_P2") (pintype "passive"))
      (node (ref "X4") (pin "4") (pinfunction "KL_4") (pintype "passive"))
    )
    (net (code "73") (name "Net-(K6B-S)") (class "Default")
      (node (ref "K6") (pin "S1") (pinfunction "S_S1") (pintype "passive"))
      (node (ref "K6") (pin "S2") (pinfunction "S_S2") (pintype "passive"))
      (node (ref "X4") (pin "3") (pinfunction "KL_3") (pintype "passive"))
    )
    (net (code "74") (name "Net-(K7A-2)") (class "Default")
      (node (ref "D8") (pin "A") (pinfunction "A_A") (pintype "passive"))
      (node (ref "K7") (pin "16") (pinfunction "2_16") (pintype "passive"))
      (node (ref "Q8") (pin "C") (pinfunction "C_C") (pintype "passive"))
      (node (ref "U8") (pin "A") (pinfunction "A_A") (pintype "passive"))
    )
    (net (code "75") (name "Net-(K7B-P)") (class "Default")
      (node (ref "K7") (pin "P1") (pinfunction "P_P1") (pintype "passive"))
      (node (ref "K7") (pin "P2") (pinfunction "P_P2") (pintype "passive"))
      (node (ref "X4") (pin "2") (pinfunction "KL_2") (pintype "passive"))
    )
    (net (code "76") (name "Net-(K7B-S)") (class "Default")
      (node (ref "K7") (pin "S1") (pinfunction "S_S1") (pintype "passive"))
      (node (ref "K7") (pin "S2") (pinfunction "S_S2") (pintype "passive"))
      (node (ref "X4") (pin "1") (pinfunction "KL_1") (pintype "passive"))
    )
    (net (code "77") (name "Net-(LED2-C)") (class "Default")
      (node (ref "LED2") (pin "K") (pinfunction "C_K") (pintype "passive"))
      (node (ref "U$1") (pin "15") (pinfunction "ASSOCIATE/DIO5_15") (pintype "bidirectional"))
    )
    (net (code "78") (name "Net-(LED2-PadA)") (class "Default")
      (node (ref "LED2") (pin "A") (pinfunction "A_A") (pintype "passive"))
      (node (ref "R40") (pin "1") (pinfunction "1_1") (pintype "passive"))
    )
    (net (code "79") (name "Net-(LED3-C)") (class "Default")
      (node (ref "LED3") (pin "K") (pinfunction "C_K") (pintype "passive"))
      (node (ref "R14") (pin "1") (pinfunction "1_1") (pintype "passive"))
    )
    (net (code "80") (name "Net-(LED4-C)") (class "Default")
      (node (ref "LED4") (pin "K") (pinfunction "C_K") (pintype "passive"))
      (node (ref "R15") (pin "2") (pinfunction "2_2") (pintype "passive"))
    )
    (net (code "81") (name "Net-(LED5-PadA)") (class "Default")
      (node (ref "LED5") (pin "A") (pinfunction "A_A") (pintype "passive"))
      (node (ref "R16") (pin "2") (pinfunction "2_2") (pintype "passive"))
    )
    (net (code "82") (name "Net-(LED6-PadA)") (class "Default")
      (node (ref "LED6") (pin "A") (pinfunction "A_A") (pintype "passive"))
      (node (ref "R33") (pin "2") (pinfunction "2_2") (pintype "passive"))
    )
    (net (code "83") (name "Net-(LED7-PadA)") (class "Default")
      (node (ref "LED7") (pin "A") (pinfunction "A_A") (pintype "passive"))
      (node (ref "R34") (pin "2") (pinfunction "2_2") (pintype "passive"))
    )
    (net (code "84") (name "Net-(Q1-PadB)") (class "Default")
      (node (ref "Q1") (pin "B") (pinfunction "B_B") (pintype "passive"))
      (node (ref "RD1") (pin "1") (pinfunction "1_1") (pintype "passive"))
    )
    (net (code "85") (name "Net-(Q2-PadB)") (class "Default")
      (node (ref "Q2") (pin "B") (pinfunction "B_B") (pintype "passive"))
      (node (ref "RD2") (pin "1") (pinfunction "1_1") (pintype "passive"))
    )
    (net (code "86") (name "Net-(Q3-PadB)") (class "Default")
      (node (ref "Q3") (pin "B") (pinfunction "B_B") (pintype "passive"))
      (node (ref "RD3") (pin "1") (pinfunction "1_1") (pintype "passive"))
    )
    (net (code "87") (name "Net-(Q4-PadB)") (class "Default")
      (node (ref "Q4") (pin "B") (pinfunction "B_B") (pintype "passive"))
      (node (ref "RD4") (pin "1") (pinfunction "1_1") (pintype "passive"))
    )
    (net (code "88") (name "Net-(Q5-PadB)") (class "Default")
      (node (ref "Q5") (pin "B") (pinfunction "B_B") (pintype "passive"))
      (node (ref "RD5") (pin "1") (pinfunction "1_1") (pintype "passive"))
    )
    (net (code "89") (name "Net-(Q6-PadB)") (class "Default")
      (node (ref "Q6") (pin "B") (pinfunction "B_B") (pintype "passive"))
      (node (ref "RD6") (pin "1") (pinfunction "1_1") (pintype "passive"))
    )
    (net (code "90") (name "Net-(Q7-PadB)") (class "Default")
      (node (ref "Q7") (pin "B") (pinfunction "B_B") (pintype "passive"))
      (node (ref "RD7") (pin "1") (pinfunction "1_1") (pintype "passive"))
    )
    (net (code "91") (name "Net-(Q8-PadB)") (class "Default")
      (node (ref "Q8") (pin "B") (pinfunction "B_B") (pintype "passive"))
      (node (ref "RD8") (pin "1") (pinfunction "1_1") (pintype "passive"))
    )
    (net (code "92") (name "Net-(S1-O)") (class "Default")
      (node (ref "RB0") (pin "1") (pinfunction "1_1") (pintype "passive"))
      (node (ref "S1") (pin "1") (pinfunction "O_1") (pintype "passive"))
      (node (ref "S2") (pin "1") (pinfunction "O_1") (pintype "passive"))
      (node (ref "S3") (pin "1") (pinfunction "O_1") (pintype "passive"))
    )
    (net (code "93") (name "Net-(S1-P)") (class "Default")
      (node (ref "RB1") (pin "2") (pinfunction "2_2") (pintype "passive"))
      (node (ref "S1") (pin "2") (pinfunction "P_2") (pintype "passive"))
    )
    (net (code "94") (name "Net-(S2-P)") (class "Default")
      (node (ref "RB2") (pin "2") (pinfunction "2_2") (pintype "passive"))
      (node (ref "S2") (pin "2") (pinfunction "P_2") (pintype "passive"))
    )
    (net (code "95") (name "Net-(S3-P)") (class "Default")
      (node (ref "RB3") (pin "2") (pinfunction "2_2") (pintype "passive"))
      (node (ref "S3") (pin "2") (pinfunction "P_2") (pintype "passive"))
    )
    (net (code "96") (name "Net-(U$1-AD0{slash}DIO0)") (class "Default")
      (node (ref "C13") (pin "2") (pinfunction "2_2") (pintype "passive"))
      (node (ref "R2") (pin "1") (pinfunction "1_1") (pintype "passive"))
      (node (ref "U$1") (pin "20") (pinfunction "AD0/DIO0_20") (pintype "bidirectional"))
    )
    (net (code "97") (name "Net-(U$1-AD1{slash}DIO1{slash}SPI_NATTN)") (class "Default")
      (node (ref "C14") (pin "2") (pinfunction "2_2") (pintype "passive"))
      (node (ref "R10") (pin "1") (pinfunction "1_1") (pintype "passive"))
      (node (ref "U$1") (pin "19") (pinfunction "AD1/DIO1/SPI_NATTN_19") (pintype "bidirectional"))
    )
    (net (code "98") (name "Net-(U$1-AD2{slash}DIO2{slash}SPI_CLK)") (class "Default")
      (node (ref "C15") (pin "2") (pinfunction "2_2") (pintype "passive"))
      (node (ref "R11") (pin "1") (pinfunction "1_1") (pintype "passive"))
      (node (ref "U$1") (pin "18") (pinfunction "AD2/DIO2/SPI_CLK_18") (pintype "bidirectional"))
    )
    (net (code "99") (name "Net-(U$1-AD3{slash}DIO3{slash}SPI_NSSEL)") (class "Default")
      (node (ref "C16") (pin "2") (pinfunction "2_2") (pintype "passive"))
      (node (ref "R12") (pin "1") (pinfunction "1_1") (pintype "passive"))
      (node (ref "U$1") (pin "17") (pinfunction "AD3/DIO3/SPI_NSSEL_17") (pintype "bidirectional"))
    )
    (net (code "100") (name "Net-(U$1-DIN{slash}NCONFIG{slash}DIO14)") (class "Default")
      (node (ref "R1") (pin "1") (pinfunction "1_1") (pintype "passive"))
      (node (ref "U$1") (pin "3") (pinfunction "DIN/NCONFIG/DIO14_3") (pintype "bidirectional"))
    )
    (net (code "101") (name "Net-(U$1-DIO4{slash}AD4{slash}SPI_MOSI)") (class "Default")
      (node (ref "C17") (pin "2") (pinfunction "2_2") (pintype "passive"))
      (node (ref "R13") (pin "1") (pinfunction "1_1") (pintype "passive"))
      (node (ref "U$1") (pin "11") (pinfunction "DIO4/AD4/SPI_MOSI_11") (pintype "bidirectional"))
    )
    (net (code "102") (name "Net-(U$1-DIO10{slash}PWM0)") (class "Default")
      (node (ref "R39") (pin "1") (pinfunction "1_1") (pintype "passive"))
      (node (ref "U$1") (pin "6") (pinfunction "DIO10/PWM0_6") (pintype "bidirectional"))
    )
    (net (code "103") (name "Net-(U$1-ON_NSLEEP{slash}DIO9)") (class "Default")
      (node (ref "LED3") (pin "A") (pinfunction "A_A") (pintype "passive"))
      (node (ref "U$1") (pin "13") (pinfunction "ON_NSLEEP/DIO9_13") (pintype "output"))
    )
    (net (code "104") (name "Net-(U1-C)") (class "Default")
      (node (ref "RL1") (pin "1") (pinfunction "1_1") (pintype "passive"))
      (node (ref "U1") (pin "K") (pinfunction "C_K") (pintype "passive"))
    )
    (net (code "105") (name "Net-(U2-C)") (class "Default")
      (node (ref "RL2") (pin "1") (pinfunction "1_1") (pintype "passive"))
      (node (ref "U2") (pin "K") (pinfunction "C_K") (pintype "passive"))
    )
    (net (code "106") (name "Net-(U3-C)") (class "Default")
      (node (ref "RL3") (pin "1") (pinfunction "1_1") (pintype "passive"))
      (node (ref "U3") (pin "K") (pinfunction "C_K") (pintype "passive"))
    )
    (net (code "107") (name "Net-(U4-C)") (class "Default")
      (node (ref "RL4") (pin "1") (pinfunction "1_1") (pintype "passive"))
      (node (ref "U4") (pin "K") (pinfunction "C_K") (pintype "passive"))
    )
    (net (code "108") (name "Net-(U5-C)") (class "Default")
      (node (ref "RL5") (pin "1") (pinfunction "1_1") (pintype "passive"))
      (node (ref "U5") (pin "K") (pinfunction "C_K") (pintype "passive"))
    )
    (net (code "109") (name "Net-(U6-C)") (class "Default")
      (node (ref "RL6") (pin "1") (pinfunction "1_1") (pintype "passive"))
      (node (ref "U6") (pin "K") (pinfunction "C_K") (pintype "passive"))
    )
    (net (code "110") (name "Net-(U7-C)") (class "Default")
      (node (ref "RL7") (pin "1") (pinfunction "1_1") (pintype "passive"))
      (node (ref "U7") (pin "K") (pinfunction "C_K") (pintype "passive"))
    )
    (net (code "111") (name "Net-(U8-C)") (class "Default")
      (node (ref "RL8") (pin "1") (pinfunction "1_1") (pintype "passive"))
      (node (ref "U8") (pin "K") (pinfunction "C_K") (pintype "passive"))
    )
    (net (code "112") (name "PE") (class "Default")
      (node (ref "23") (pin "1") (pinfunction "E_1") (pintype "passive"))
      (node (ref "C1") (pin "1") (pinfunction "1_1") (pintype "passive"))
      (node (ref "C10") (pin "2") (pinfunction "2_2") (pintype "passive"))
      (node (ref "C11") (pin "2") (pinfunction "2_2") (pintype "passive"))
      (node (ref "C13") (pin "1") (pinfunction "1_1") (pintype "passive"))
      (node (ref "C14") (pin "1") (pinfunction "1_1") (pintype "passive"))
      (node (ref "C15") (pin "1") (pinfunction "1_1") (pintype "passive"))
      (node (ref "C16") (pin "1") (pinfunction "1_1") (pintype "passive"))
      (node (ref "C17") (pin "1") (pinfunction "1_1") (pintype "passive"))
      (node (ref "C18") (pin "-") (pinfunction "-_-") (pintype "passive"))
      (node (ref "C2") (pin "1") (pinfunction "1_1") (pintype "passive"))
      (node (ref "C20") (pin "-") (pinfunction "-_-") (pintype "passive"))
      (node (ref "C3") (pin "1") (pinfunction "1_1") (pintype "passive"))
      (node (ref "C4") (pin "1") (pinfunction "1_1") (pintype "passive"))
      (node (ref "C5") (pin "1") (pinfunction "1_1") (pintype "passive"))
      (node (ref "C6") (pin "1") (pinfunction "1_1") (pintype "passive"))
      (node (ref "C7") (pin "1") (pinfunction "1_1") (pintype "passive"))
      (node (ref "C8") (pin "1") (pinfunction "1_1") (pintype "passive"))
      (node (ref "C9") (pin "-") (pinfunction "-_-") (pintype "passive"))
      (node (ref "IC1") (pin "11") (pinfunction "GND_11") (pintype "power_in"))
      (node (ref "IC1") (pin "31") (pinfunction "AGND_31") (pintype "power_in"))
      (node (ref "IC3") (pin "6") (pinfunction "INH_6") (pintype "input"))
      (node (ref "IC3") (pin "7") (pinfunction "VEE_7") (pintype "power_in"))
      (node (ref "IC3") (pin "8") (pinfunction "GND_8") (pintype "power_in"))
      (node (ref "IC4") (pin "GND") (pinfunction "GND_GND") (pintype "input"))
      (node (ref "IC5") (pin "GND") (pinfunction "GND_GND") (pintype "input"))
      (node (ref "IC6") (pin "GND") (pinfunction "GND_GND") (pintype "input"))
      (node (ref "IC7") (pin "12") (pinfunction "GND_12") (pintype "power_in"))
      (node (ref "ISP") (pin "10") (pinfunction "10_10") (pintype "passive"))
      (node (ref "ISP") (pin "4") (pinfunction "4_4") (pintype "passive"))
      (node (ref "ISP") (pin "6") (pinfunction "6_6") (pintype "passive"))
      (node (ref "ISP") (pin "8") (pinfunction "8_8") (pintype "passive"))
      (node (ref "JP1") (pin "1") (pinfunction "1_1") (pintype "passive"))
      (node (ref "JP1") (pin "10") (pinfunction "10_10") (pintype "passive"))
      (node (ref "JP1") (pin "16") (pinfunction "16_16") (pintype "passive"))
      (node (ref "JP1") (pin "7") (pinfunction "7_7") (pintype "passive"))
      (node (ref "JP1") (pin "8") (pinfunction "8_8") (pintype "passive"))
      (node (ref "JP1") (pin "9") (pinfunction "9_9") (pintype "passive"))
      (node (ref "K0") (pin "1") (pinfunction "1_1") (pintype "passive"))
      (node (ref "K1") (pin "1") (pinfunction "1_1") (pintype "passive"))
      (node (ref "K2") (pin "1") (pinfunction "1_1") (pintype "passive"))
      (node (ref "K3") (pin "1") (pinfunction "1_1") (pintype "passive"))
      (node (ref "K4") (pin "1") (pinfunction "1_1") (pintype "passive"))
      (node (ref "K5") (pin "1") (pinfunction "1_1") (pintype "passive"))
      (node (ref "K6") (pin "1") (pinfunction "1_1") (pintype "passive"))
      (node (ref "K7") (pin "1") (pinfunction "1_1") (pintype "passive"))
      (node (ref "Q22") (pin "1") (pinfunction "E_1") (pintype "passive"))
      (node (ref "R10") (pin "2") (pinfunction "2_2") (pintype "passive"))
      (node (ref "R11") (pin "2") (pinfunction "2_2") (pintype "passive"))
      (node (ref "R12") (pin "2") (pinfunction "2_2") (pintype "passive"))
      (node (ref "R13") (pin "2") (pinfunction "2_2") (pintype "passive"))
      (node (ref "R14") (pin "2") (pinfunction "2_2") (pintype "passive"))
      (node (ref "R15") (pin "1") (pinfunction "1_1") (pintype "passive"))
      (node (ref "R17") (pin "A") (pinfunction "A_A") (pintype "passive"))
      (node (ref "R2") (pin "2") (pinfunction "2_2") (pintype "passive"))
      (node (ref "R3") (pin "1") (pinfunction "1_1") (pintype "passive"))
      (node (ref "R38") (pin "1") (pinfunction "1_1") (pintype "passive"))
      (node (ref "R4") (pin "1") (pinfunction "1_1") (pintype "passive"))
      (node (ref "RB1") (pin "1") (pinfunction "1_1") (pintype "passive"))
      (node (ref "RB2") (pin "1") (pinfunction "1_1") (pintype "passive"))
      (node (ref "RB3") (pin "1") (pinfunction "1_1") (pintype "passive"))
      (node (ref "RL1") (pin "2") (pinfunction "2_2") (pintype "passive"))
      (node (ref "RL2") (pin "2") (pinfunction "2_2") (pintype "passive"))
      (node (ref "RL3") (pin "2") (pinfunction "2_2") (pintype "passive"))
      (node (ref "RL4") (pin "2") (pinfunction "2_2") (pintype "passive"))
      (node (ref "RL5") (pin "2") (pinfunction "2_2") (pintype "passive"))
      (node (ref "RL6") (pin "2") (pinfunction "2_2") (pintype "passive"))
      (node (ref "RL7") (pin "2") (pinfunction "2_2") (pintype "passive"))
      (node (ref "RL8") (pin "2") (pinfunction "2_2") (pintype "passive"))
      (node (ref "U$1") (pin "10") (pinfunction "GND_10") (pintype "input"))
      (node (ref "X5") (pin "2") (pinfunction "KL_2") (pintype "passive"))
    )
    (net (code "113") (name "VRef") (class "Default")
      (node (ref "C6") (pin "2") (pinfunction "2_2") (pintype "passive"))
      (node (ref "IC1") (pin "30") (pinfunction "AVCC_30") (pintype "power_in"))
      (node (ref "IC1") (pin "32") (pinfunction "AREF_32") (pintype "power_in"))
      (node (ref "IC5") (pin "OUT") (pinfunction "OUT_OUT") (pintype "passive"))
      (node (ref "R3") (pin "2") (pinfunction "2_2") (pintype "passive"))
      (node (ref "RB0") (pin "2") (pinfunction "2_2") (pintype "passive"))
      (node (ref "U$1") (pin "14") (pinfunction "VREF_14") (pintype "input"))
    )
    (net (code "114") (name "unconnected-(IC1-(ADC0)PA0-Pad40)") (class "Default")
      (node (ref "IC1") (pin "40") (pinfunction "(ADC0)PA0_40") (pintype "bidirectional"))
    )
    (net (code "115") (name "unconnected-(IC1-(ADC1)PA1-Pad39)") (class "Default")
      (node (ref "IC1") (pin "39") (pinfunction "(ADC1)PA1_39") (pintype "bidirectional"))
    )
    (net (code "116") (name "unconnected-(IC1-(ADC2)PA2-Pad38)") (class "Default")
      (node (ref "IC1") (pin "38") (pinfunction "(ADC2)PA2_38") (pintype "bidirectional"))
    )
    (net (code "117") (name "unconnected-(IC1-(ADC3)PA3-Pad37)") (class "Default")
      (node (ref "IC1") (pin "37") (pinfunction "(ADC3)PA3_37") (pintype "bidirectional"))
    )
    (net (code "118") (name "unconnected-(IC1-(ADC4)PA4-Pad36)") (class "Default")
      (node (ref "IC1") (pin "36") (pinfunction "(ADC4)PA4_36") (pintype "bidirectional"))
    )
    (net (code "119") (name "unconnected-(IC1-(ADC5)PA5-Pad35)") (class "Default")
      (node (ref "IC1") (pin "35") (pinfunction "(ADC5)PA5_35") (pintype "bidirectional"))
    )
    (net (code "120") (name "unconnected-(IC1-(ADC6)PA6-Pad34)") (class "Default")
      (node (ref "IC1") (pin "34") (pinfunction "(ADC6)PA6_34") (pintype "bidirectional"))
    )
    (net (code "121") (name "unconnected-(IC1-(ADC7)PA7-Pad33)") (class "Default")
      (node (ref "IC1") (pin "33") (pinfunction "(ADC7)PA7_33") (pintype "bidirectional"))
    )
    (net (code "122") (name "unconnected-(K0B-O-PadO1)") (class "Default")
      (node (ref "K0") (pin "O1") (pinfunction "O_O1") (pintype "passive"))
    )
    (net (code "123") (name "unconnected-(K0C-O-PadO2)") (class "Default")
      (node (ref "K0") (pin "O2") (pinfunction "O_O2") (pintype "passive"))
    )
    (net (code "124") (name "unconnected-(K1B-O-PadO1)") (class "Default")
      (node (ref "K1") (pin "O1") (pinfunction "O_O1") (pintype "passive"))
    )
    (net (code "125") (name "unconnected-(K1C-O-PadO2)") (class "Default")
      (node (ref "K1") (pin "O2") (pinfunction "O_O2") (pintype "passive"))
    )
    (net (code "126") (name "unconnected-(K2B-O-PadO1)") (class "Default")
      (node (ref "K2") (pin "O1") (pinfunction "O_O1") (pintype "passive"))
    )
    (net (code "127") (name "unconnected-(K2C-O-PadO2)") (class "Default")
      (node (ref "K2") (pin "O2") (pinfunction "O_O2") (pintype "passive"))
    )
    (net (code "128") (name "unconnected-(K3B-O-PadO1)") (class "Default")
      (node (ref "K3") (pin "O1") (pinfunction "O_O1") (pintype "passive"))
    )
    (net (code "129") (name "unconnected-(K3C-O-PadO2)") (class "Default")
      (node (ref "K3") (pin "O2") (pinfunction "O_O2") (pintype "passive"))
    )
    (net (code "130") (name "unconnected-(K4B-O-PadO1)") (class "Default")
      (node (ref "K4") (pin "O1") (pinfunction "O_O1") (pintype "passive"))
    )
    (net (code "131") (name "unconnected-(K4C-O-PadO2)") (class "Default")
      (node (ref "K4") (pin "O2") (pinfunction "O_O2") (pintype "passive"))
    )
    (net (code "132") (name "unconnected-(K5B-O-PadO1)") (class "Default")
      (node (ref "K5") (pin "O1") (pinfunction "O_O1") (pintype "passive"))
    )
    (net (code "133") (name "unconnected-(K5C-O-PadO2)") (class "Default")
      (node (ref "K5") (pin "O2") (pinfunction "O_O2") (pintype "passive"))
    )
    (net (code "134") (name "unconnected-(K6B-O-PadO1)") (class "Default")
      (node (ref "K6") (pin "O1") (pinfunction "O_O1") (pintype "passive"))
    )
    (net (code "135") (name "unconnected-(K6C-O-PadO2)") (class "Default")
      (node (ref "K6") (pin "O2") (pinfunction "O_O2") (pintype "passive"))
    )
    (net (code "136") (name "unconnected-(K7B-O-PadO1)") (class "Default")
      (node (ref "K7") (pin "O1") (pinfunction "O_O1") (pintype "passive"))
    )
    (net (code "137") (name "unconnected-(K7C-O-PadO2)") (class "Default")
      (node (ref "K7") (pin "O2") (pinfunction "O_O2") (pintype "passive"))
    )
    (net (code "138") (name "unconnected-(S1-S-Pad3)") (class "Default")
      (node (ref "S1") (pin "3") (pinfunction "S_3") (pintype "passive"))
    )
    (net (code "139") (name "unconnected-(S2-S-Pad3)") (class "Default")
      (node (ref "S2") (pin "3") (pinfunction "S_3") (pintype "passive"))
    )
    (net (code "140") (name "unconnected-(S3-S-Pad3)") (class "Default")
      (node (ref "S3") (pin "3") (pinfunction "S_3") (pintype "passive"))
    )
    (net (code "141") (name "unconnected-(U$1-DIO11{slash}PWM1-Pad7)") (class "Default")
      (node (ref "U$1") (pin "7") (pinfunction "DIO11/PWM1_7") (pintype "bidirectional"))
    )
    (net (code "142") (name "unconnected-(U$1-DIO12{slash}SPI_MISO-Pad4)") (class "Default")
      (node (ref "U$1") (pin "4") (pinfunction "DIO12/SPI_MISO_4") (pintype "bidirectional"))
    )
    (net (code "143") (name "unconnected-(U$1-DOUT{slash}DIO13-Pad2)") (class "Default")
      (node (ref "U$1") (pin "2") (pinfunction "DOUT/DIO13_2") (pintype "bidirectional"))
    )
    (net (code "144") (name "unconnected-(U$1-NCTS{slash}DIO7-Pad12)") (class "Default")
      (node (ref "U$1") (pin "12") (pinfunction "NCTS/DIO7_12") (pintype "bidirectional"))
    )
    (net (code "145") (name "unconnected-(U$1-NDTR{slash}SLEEP_RQ{slash}DIO8-Pad9)") (class "Default")
      (node (ref "U$1") (pin "9") (pinfunction "NDTR/SLEEP_RQ/DIO8_9") (pintype "bidirectional"))
    )
    (net (code "146") (name "unconnected-(U$1-NRESET-Pad5)") (class "Default")
      (node (ref "U$1") (pin "5") (pinfunction "NRESET_5") (pintype "input"))
    )
    (net (code "147") (name "unconnected-(U$1-NRTS{slash}DIO6-Pad16)") (class "Default")
      (node (ref "U$1") (pin "16") (pinfunction "NRTS/DIO6_16") (pintype "bidirectional"))
    )
    (net (code "148") (name "unconnected-(U$1-RESERVED-Pad8)") (class "Default")
      (node (ref "U$1") (pin "8") (pinfunction "RESERVED_8") (pintype "bidirectional"))
    )
  )
)
